# max17222evk.net
KiCad netlist of a schematic drawn in EAGLE
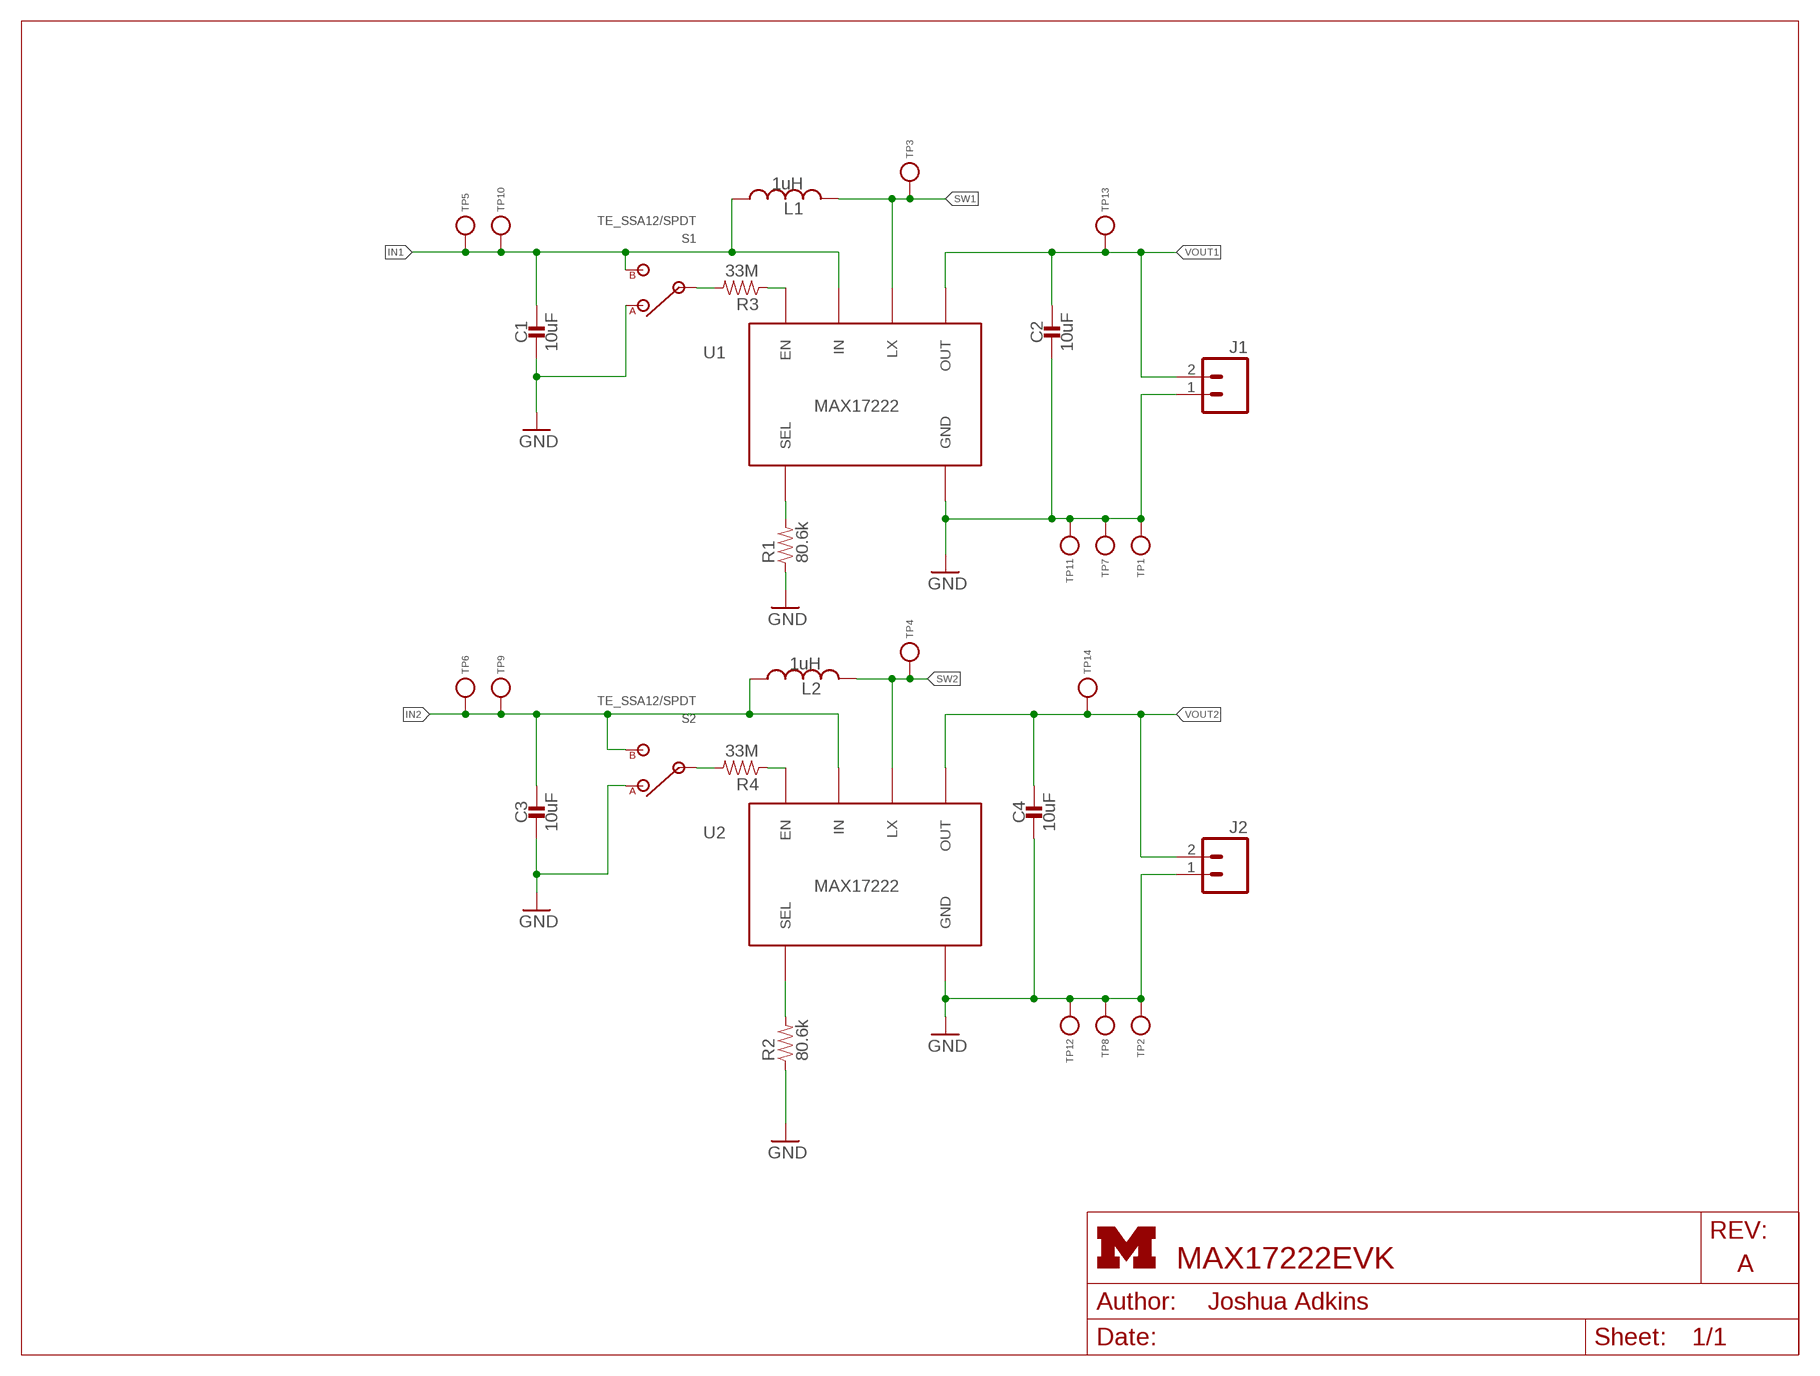
[diagram p0: schematic, sheet 1]

(export (version "E")
  (design (tool "Eeschema 10.0.6"))
  (components
    (comp (ref "C1")
      (value "10uF")
      (footprint "eagle-import:0603_CAP")
      (libsource (lib "eagle-import") (part "CAPACITOR0603_CAP"))
    )
    (comp (ref "C2")
      (value "10uF")
      (footprint "eagle-import:0603_CAP")
      (libsource (lib "eagle-import") (part "CAPACITOR0603_CAP"))
    )
    (comp (ref "C3")
      (value "10uF")
      (footprint "eagle-import:0603_CAP")
      (libsource (lib "eagle-import") (part "CAPACITOR0603_CAP"))
    )
    (comp (ref "C4")
      (value "10uF")
      (footprint "eagle-import:0603_CAP")
      (libsource (lib "eagle-import") (part "CAPACITOR0603_CAP"))
    )
    (comp (ref "J1")
      (value "M023.5MM")
      (footprint "eagle-import:SCREWTERMINAL-3.5MM-2")
      (libsource (lib "eagle-import") (part "M023.5MM"))
    )
    (comp (ref "J2")
      (value "M023.5MM")
      (footprint "eagle-import:SCREWTERMINAL-3.5MM-2")
      (libsource (lib "eagle-import") (part "M023.5MM"))
    )
    (comp (ref "L1")
      (value "1uH")
      (footprint "eagle-import:IHL-2525CZ")
      (libsource (lib "eagle-import") (part "INDUCTORIHL2525CZ"))
    )
    (comp (ref "L2")
      (value "1uH")
      (footprint "eagle-import:DFE322512C")
      (libsource (lib "eagle-import") (part "INDUCTORDFE322512C"))
    )
    (comp (ref "R1")
      (value "80.6k")
      (footprint "eagle-import:0603-RES")
      (libsource (lib "eagle-import") (part "RESISTOR0603_RES"))
    )
    (comp (ref "R2")
      (value "80.6k")
      (footprint "eagle-import:0603-RES")
      (libsource (lib "eagle-import") (part "RESISTOR0603_RES"))
    )
    (comp (ref "R3")
      (value "33M")
      (footprint "eagle-import:0603-RES")
      (libsource (lib "eagle-import") (part "RESISTOR0603_RES"))
    )
    (comp (ref "R4")
      (value "33M")
      (footprint "eagle-import:0603-RES")
      (libsource (lib "eagle-import") (part "RESISTOR0603_RES"))
    )
    (comp (ref "S1")
      (value "TE_SSA12/SPDT")
      (footprint "eagle-import:TE_SSA12_SPDT")
      (libsource (lib "eagle-import") (part "TE_SSA12/SPDT"))
    )
    (comp (ref "S2")
      (value "TE_SSA12/SPDT")
      (footprint "eagle-import:TE_SSA12_SPDT")
      (libsource (lib "eagle-import") (part "TE_SSA12/SPDT"))
    )
    (comp (ref "TP1")
      (value "TEST_POINT_0.112IN")
      (footprint "eagle-import:TESTPOINT_0.112IN")
      (libsource (lib "eagle-import") (part "TEST_POINT_0.112IN"))
    )
    (comp (ref "TP2")
      (value "TEST_POINT_0.112IN")
      (footprint "eagle-import:TESTPOINT_0.112IN")
      (libsource (lib "eagle-import") (part "TEST_POINT_0.112IN"))
    )
    (comp (ref "TP3")
      (value "TEST_POINT_0.040IN")
      (footprint "eagle-import:TESTPOINT_0.040IN")
      (libsource (lib "eagle-import") (part "TEST_POINT_0.040IN"))
    )
    (comp (ref "TP4")
      (value "TEST_POINT_0.040IN")
      (footprint "eagle-import:TESTPOINT_0.040IN")
      (libsource (lib "eagle-import") (part "TEST_POINT_0.040IN"))
    )
    (comp (ref "TP5")
      (value "TEST_POINT_0.040IN")
      (footprint "eagle-import:TESTPOINT_0.040IN")
      (libsource (lib "eagle-import") (part "TEST_POINT_0.040IN"))
    )
    (comp (ref "TP6")
      (value "TEST_POINT_0.040IN")
      (footprint "eagle-import:TESTPOINT_0.040IN")
      (libsource (lib "eagle-import") (part "TEST_POINT_0.040IN"))
    )
    (comp (ref "TP7")
      (value "TEST_POINT_0.040IN")
      (footprint "eagle-import:TESTPOINT_0.040IN")
      (libsource (lib "eagle-import") (part "TEST_POINT_0.040IN"))
    )
    (comp (ref "TP8")
      (value "TEST_POINT_0.040IN")
      (footprint "eagle-import:TESTPOINT_0.040IN")
      (libsource (lib "eagle-import") (part "TEST_POINT_0.040IN"))
    )
    (comp (ref "TP9")
      (value "TEST_POINT_0.040IN")
      (footprint "eagle-import:TESTPOINT_0.040IN")
      (libsource (lib "eagle-import") (part "TEST_POINT_0.040IN"))
    )
    (comp (ref "TP10")
      (value "TEST_POINT_0.040IN")
      (footprint "eagle-import:TESTPOINT_0.040IN")
      (libsource (lib "eagle-import") (part "TEST_POINT_0.040IN"))
    )
    (comp (ref "TP11")
      (value "TEST_POINT_0.112IN")
      (footprint "eagle-import:TESTPOINT_0.112IN")
      (libsource (lib "eagle-import") (part "TEST_POINT_0.112IN"))
    )
    (comp (ref "TP12")
      (value "TEST_POINT_0.112IN")
      (footprint "eagle-import:TESTPOINT_0.112IN")
      (libsource (lib "eagle-import") (part "TEST_POINT_0.112IN"))
    )
    (comp (ref "TP13")
      (value "TEST_POINT_0.040IN")
      (footprint "eagle-import:TESTPOINT_0.040IN")
      (libsource (lib "eagle-import") (part "TEST_POINT_0.040IN"))
    )
    (comp (ref "TP14")
      (value "TEST_POINT_0.040IN")
      (footprint "eagle-import:TESTPOINT_0.040IN")
      (libsource (lib "eagle-import") (part "TEST_POINT_0.040IN"))
    )
    (comp (ref "U1")
      (value "MAX17222")
      (footprint "eagle-import:UDFN-6-MAXIM")
      (fields (field (name "MANUFACTURER") "MAXIM INTEGRATED"))
      (libsource (lib "eagle-import") (part "MAX17222"))
    )
    (comp (ref "U2")
      (value "MAX17222")
      (footprint "eagle-import:UDFN-6-MAXIM")
      (fields (field (name "MANUFACTURER") "MAXIM INTEGRATED"))
      (libsource (lib "eagle-import") (part "MAX17222"))
    )
  )
  (nets
    (net (code "1") (name "GND") (class "Default")
      (node (ref "C1") (pin "2") (pinfunction "2_2") (pintype "bidirectional"))
      (node (ref "C2") (pin "2") (pinfunction "2_2") (pintype "bidirectional"))
      (node (ref "C3") (pin "2") (pinfunction "2_2") (pintype "bidirectional"))
      (node (ref "C4") (pin "2") (pinfunction "2_2") (pintype "bidirectional"))
      (node (ref "J1") (pin "1") (pinfunction "1_1") (pintype "passive"))
      (node (ref "J2") (pin "1") (pinfunction "1_1") (pintype "passive"))
      (node (ref "R1") (pin "1") (pinfunction "1_1") (pintype "passive"))
      (node (ref "R2") (pin "1") (pinfunction "1_1") (pintype "passive"))
      (node (ref "S1") (pin "1") (pinfunction "A_1") (pintype "bidirectional"))
      (node (ref "S2") (pin "1") (pinfunction "A_1") (pintype "bidirectional"))
      (node (ref "TP1") (pin "1") (pinfunction "TESTPOINT_1") (pintype "bidirectional"))
      (node (ref "TP11") (pin "1") (pinfunction "TESTPOINT_1") (pintype "bidirectional"))
      (node (ref "TP12") (pin "1") (pinfunction "TESTPOINT_1") (pintype "bidirectional"))
      (node (ref "TP2") (pin "1") (pinfunction "TESTPOINT_1") (pintype "bidirectional"))
      (node (ref "TP7") (pin "TESTPOINT") (pinfunction "TESTPOINT_TESTPOINT") (pintype "bidirectional"))
      (node (ref "TP8") (pin "TESTPOINT") (pinfunction "TESTPOINT_TESTPOINT") (pintype "bidirectional"))
      (node (ref "U1") (pin "3") (pinfunction "GND_3") (pintype "bidirectional"))
      (node (ref "U2") (pin "3") (pinfunction "GND_3") (pintype "bidirectional"))
    )
    (net (code "2") (name "IN1") (class "Default")
      (node (ref "C1") (pin "1") (pinfunction "1_1") (pintype "bidirectional"))
      (node (ref "L1") (pin "P$1") (pinfunction "1_P$1") (pintype "bidirectional"))
      (node (ref "S1") (pin "2") (pinfunction "B_2") (pintype "bidirectional"))
      (node (ref "TP10") (pin "TESTPOINT") (pinfunction "TESTPOINT_TESTPOINT") (pintype "bidirectional"))
      (node (ref "TP5") (pin "TESTPOINT") (pinfunction "TESTPOINT_TESTPOINT") (pintype "bidirectional"))
      (node (ref "U1") (pin "5") (pinfunction "IN_5") (pintype "bidirectional"))
    )
    (net (code "3") (name "IN2") (class "Default")
      (node (ref "C3") (pin "1") (pinfunction "1_1") (pintype "bidirectional"))
      (node (ref "L2") (pin "P$1") (pinfunction "1_P$1") (pintype "bidirectional"))
      (node (ref "S2") (pin "2") (pinfunction "B_2") (pintype "bidirectional"))
      (node (ref "TP6") (pin "TESTPOINT") (pinfunction "TESTPOINT_TESTPOINT") (pintype "bidirectional"))
      (node (ref "TP9") (pin "TESTPOINT") (pinfunction "TESTPOINT_TESTPOINT") (pintype "bidirectional"))
      (node (ref "U2") (pin "5") (pinfunction "IN_5") (pintype "bidirectional"))
    )
    (net (code "4") (name "Net-(R3-Pad2)") (class "Default")
      (node (ref "R3") (pin "2") (pinfunction "2_2") (pintype "passive"))
      (node (ref "S1") (pin "IN") (pinfunction "IN_IN") (pintype "bidirectional"))
    )
    (net (code "5") (name "Net-(R4-Pad2)") (class "Default")
      (node (ref "R4") (pin "2") (pinfunction "2_2") (pintype "passive"))
      (node (ref "S2") (pin "IN") (pinfunction "IN_IN") (pintype "bidirectional"))
    )
    (net (code "6") (name "Net-(U1-EN)") (class "Default")
      (node (ref "R3") (pin "1") (pinfunction "1_1") (pintype "passive"))
      (node (ref "U1") (pin "6") (pinfunction "EN_6") (pintype "bidirectional"))
    )
    (net (code "7") (name "Net-(U1-SEL)") (class "Default")
      (node (ref "R1") (pin "2") (pinfunction "2_2") (pintype "passive"))
      (node (ref "U1") (pin "4") (pinfunction "SEL_4") (pintype "bidirectional"))
    )
    (net (code "8") (name "Net-(U2-EN)") (class "Default")
      (node (ref "R4") (pin "1") (pinfunction "1_1") (pintype "passive"))
      (node (ref "U2") (pin "6") (pinfunction "EN_6") (pintype "bidirectional"))
    )
    (net (code "9") (name "Net-(U2-SEL)") (class "Default")
      (node (ref "R2") (pin "2") (pinfunction "2_2") (pintype "passive"))
      (node (ref "U2") (pin "4") (pinfunction "SEL_4") (pintype "bidirectional"))
    )
    (net (code "10") (name "SW1") (class "Default")
      (node (ref "L1") (pin "P$2") (pinfunction "2_P$2") (pintype "bidirectional"))
      (node (ref "TP3") (pin "TESTPOINT") (pinfunction "TESTPOINT_TESTPOINT") (pintype "bidirectional"))
      (node (ref "U1") (pin "2") (pinfunction "LX_2") (pintype "bidirectional"))
    )
    (net (code "11") (name "SW2") (class "Default")
      (node (ref "L2") (pin "P$2") (pinfunction "2_P$2") (pintype "bidirectional"))
      (node (ref "TP4") (pin "TESTPOINT") (pinfunction "TESTPOINT_TESTPOINT") (pintype "bidirectional"))
      (node (ref "U2") (pin "2") (pinfunction "LX_2") (pintype "bidirectional"))
    )
    (net (code "12") (name "VOUT1") (class "Default")
      (node (ref "C2") (pin "1") (pinfunction "1_1") (pintype "bidirectional"))
      (node (ref "J1") (pin "2") (pinfunction "2_2") (pintype "passive"))
      (node (ref "TP13") (pin "TESTPOINT") (pinfunction "TESTPOINT_TESTPOINT") (pintype "bidirectional"))
      (node (ref "U1") (pin "1") (pinfunction "OUT_1") (pintype "bidirectional"))
    )
    (net (code "13") (name "VOUT2") (class "Default")
      (node (ref "C4") (pin "1") (pinfunction "1_1") (pintype "bidirectional"))
      (node (ref "J2") (pin "2") (pinfunction "2_2") (pintype "passive"))
      (node (ref "TP14") (pin "TESTPOINT") (pinfunction "TESTPOINT_TESTPOINT") (pintype "bidirectional"))
      (node (ref "U2") (pin "1") (pinfunction "OUT_1") (pintype "bidirectional"))
    )
  )
)
